# knxhome-lqfp32-v2.net
KiCad netlist of a schematic drawn in EAGLE
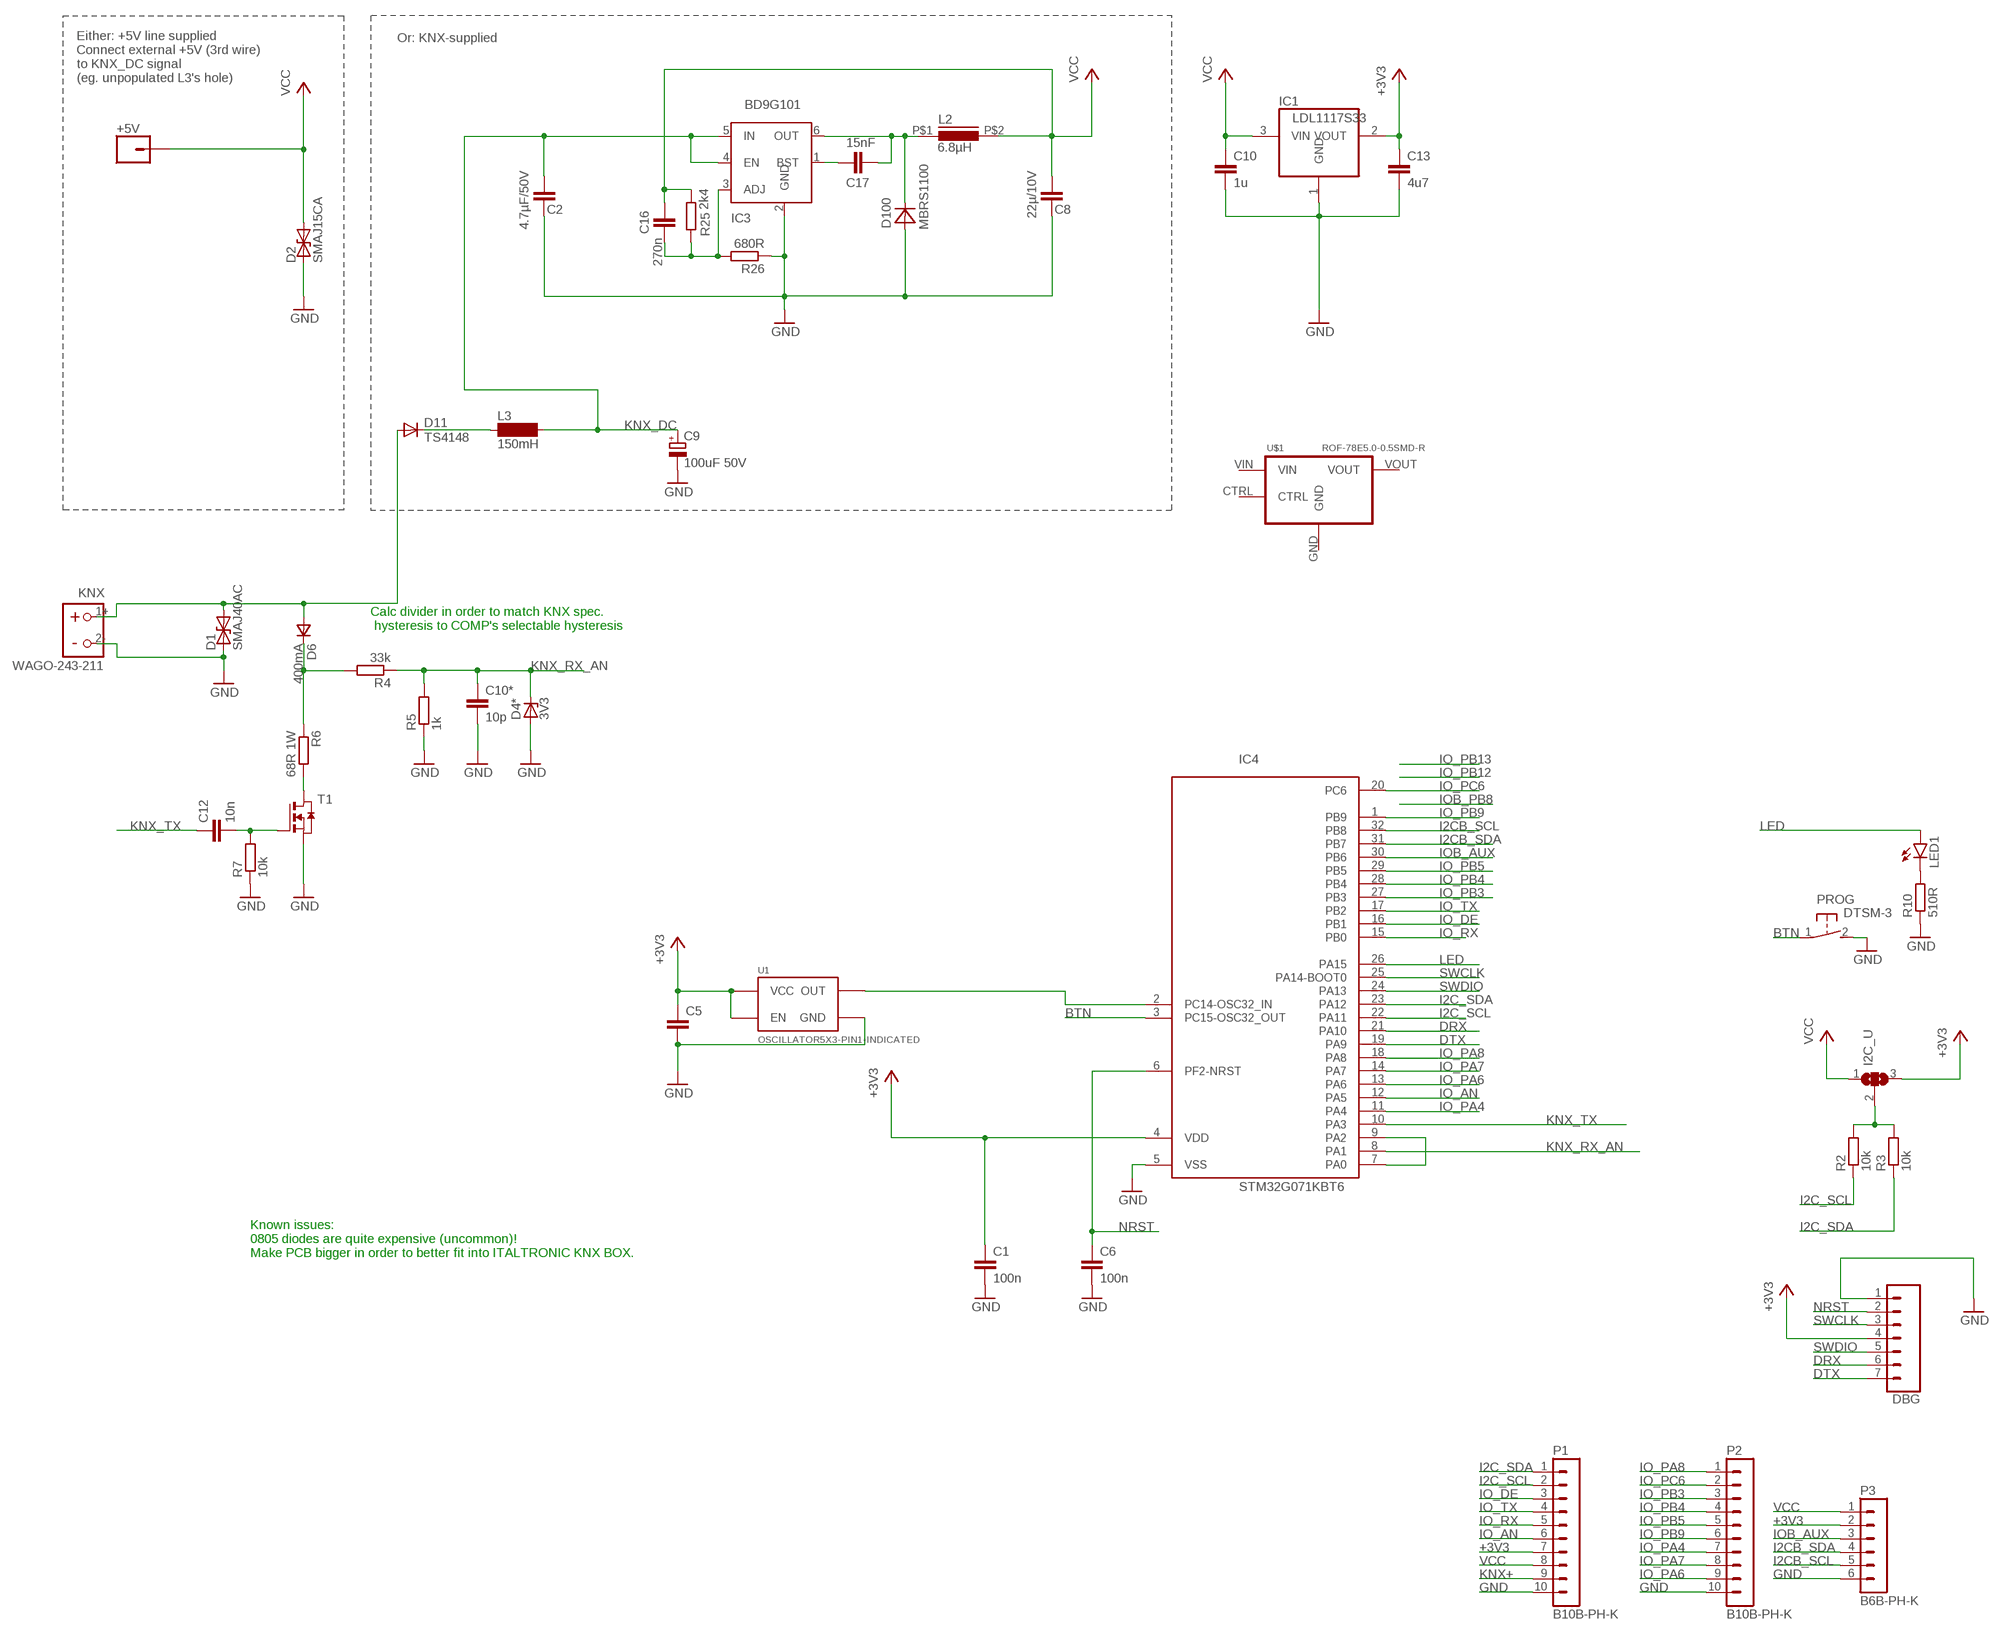
[diagram p0: schematic, sheet 1]

(export (version "E")
  (design (tool "Eeschema 10.0.6"))
  (components
    (comp (ref "+5V")
      (value "CONN_01PTH_LONGPAD")
      (footprint "eagle-import:1X01_LONGPAD")
      (libsource (lib "eagle-import") (part "CONN_01PTH_LONGPAD"))
    )
    (comp (ref "C1")
      (value "100n")
      (footprint "eagle-import:C0805")
      (libsource (lib "eagle-import") (part "C-EUC0805"))
    )
    (comp (ref "C2")
      (value "4.7µF/50V")
      (footprint "eagle-import:C0805")
      (libsource (lib "eagle-import") (part "C-EUC0805"))
    )
    (comp (ref "C5")
      (value "C-EUC0805")
      (footprint "eagle-import:C0805")
      (libsource (lib "eagle-import") (part "C-EUC0805"))
    )
    (comp (ref "C6")
      (value "100n")
      (footprint "eagle-import:C0805")
      (libsource (lib "eagle-import") (part "C-EUC0805"))
    )
    (comp (ref "C8")
      (value "22µ/10V")
      (footprint "eagle-import:C0805")
      (libsource (lib "eagle-import") (part "C-EUC0805"))
    )
    (comp (ref "C9")
      (value "100uF 50V")
      (footprint "eagle-import:E3,5-8")
      (libsource (lib "eagle-import") (part "CPOL-EUE3.5-8"))
    )
    (comp (ref "C10")
      (value "1u")
      (footprint "eagle-import:C0805")
      (libsource (lib "eagle-import") (part "C-EUC0805"))
    )
    (comp (ref "C10*")
      (value "10p")
      (footprint "eagle-import:C0805")
      (libsource (lib "eagle-import") (part "C-EUC0805"))
    )
    (comp (ref "C12")
      (value "10n")
      (footprint "eagle-import:C0805")
      (libsource (lib "eagle-import") (part "C-EUC0805"))
    )
    (comp (ref "C13")
      (value "4u7")
      (footprint "eagle-import:C0805")
      (libsource (lib "eagle-import") (part "C-EUC0805"))
    )
    (comp (ref "C16")
      (value "270n")
      (footprint "eagle-import:C0805")
      (libsource (lib "eagle-import") (part "C-EUC0805"))
    )
    (comp (ref "C17")
      (value "15nF")
      (footprint "eagle-import:C0805")
      (libsource (lib "eagle-import") (part "C-EUC0805"))
    )
    (comp (ref "D1")
      (value "SMAJ40AC")
      (footprint "eagle-import:DO-214AC")
      (libsource (lib "eagle-import") (part "SMAJ40AC"))
    )
    (comp (ref "D2")
      (value "SMAJ15CA")
      (footprint "eagle-import:DO-214AC")
      (libsource (lib "eagle-import") (part "SMAJ40AC"))
    )
    (comp (ref "D4*")
      (value "3V3")
      (footprint "eagle-import:SOT23")
      (libsource (lib "eagle-import") (part "ZENER-DIODESOT23"))
    )
    (comp (ref "D6")
      (value "400mA")
      (footprint "eagle-import:SOD323")
      (fields (field (name "MPN") "CDSOD323-T05C"))
      (libsource (lib "eagle-import") (part "DSOD323"))
    )
    (comp (ref "D11")
      (value "TS4148")
      (footprint "eagle-import:D0805")
      (libsource (lib "eagle-import") (part "DIODE-D0805"))
    )
    (comp (ref "D100")
      (value "MBRS1100")
      (footprint "eagle-import:SMA")
      (libsource (lib "eagle-import") (part "MBRA340T3"))
    )
    (comp (ref "DBG")
      (value "CONN_07LOCK")
      (footprint "eagle-import:1X07_LOCK")
      (libsource (lib "eagle-import") (part "CONN_07LOCK"))
    )
    (comp (ref "I2C_U")
      (value "SJ2W")
      (footprint "eagle-import:SJ_2")
      (libsource (lib "eagle-import") (part "SJ2W"))
    )
    (comp (ref "IC1")
      (value "LDL1117S33")
      (footprint "eagle-import:SOT223")
      (fields (field (name "MPN") "REG1117"))
      (libsource (lib "eagle-import") (part "REG1117"))
    )
    (comp (ref "IC3")
      (value "BD9G101")
      (footprint "eagle-import:SOT23-6")
      (libsource (lib "eagle-import") (part "BD9G101GBD9G101G-SOT23-6"))
    )
    (comp (ref "IC4")
      (value "STM32G071KBT6")
      (footprint "eagle-import:LQFP32")
      (libsource (lib "eagle-import") (part "STM32G071KBT6"))
    )
    (comp (ref "KNX")
      (value "WAGO-243-211")
      (footprint "eagle-import:WAGO-243-211")
      (libsource (lib "eagle-import") (part "WAGO-243-211"))
    )
    (comp (ref "L2")
      (value "6.8µH")
      (footprint "eagle-import:PIS2812")
      (libsource (lib "eagle-import") (part "IND_FASTRON_1616FPS"))
    )
    (comp (ref "L3")
      (value "150mH")
      (footprint "eagle-import:BS11_LIEGEND")
      (libsource (lib "eagle-import") (part "SD12BS11_LIEGEND"))
    )
    (comp (ref "LED1")
      (value "LEDCHIP-LED0805")
      (footprint "eagle-import:CHIP-LED0805")
      (libsource (lib "eagle-import") (part "LEDCHIP-LED0805"))
    )
    (comp (ref "P1")
      (value "B10B-PH-K")
      (footprint "eagle-import:B10B-PH-K")
      (libsource (lib "eagle-import") (part "B10B-PH-K"))
    )
    (comp (ref "P2")
      (value "B10B-PH-K")
      (footprint "eagle-import:B10B-PH-K")
      (libsource (lib "eagle-import") (part "B10B-PH-K"))
    )
    (comp (ref "P3")
      (value "B6B-PH-K")
      (footprint "eagle-import:B6B-PH-K")
      (libsource (lib "eagle-import") (part "B6B-PH-K"))
    )
    (comp (ref "PROG")
      (value "DTSM-3")
      (footprint "eagle-import:DTSM-3")
      (libsource (lib "eagle-import") (part "DTSM-3"))
    )
    (comp (ref "R2")
      (value "10k")
      (footprint "eagle-import:R0805")
      (libsource (lib "eagle-import") (part "R-EU_R0805"))
    )
    (comp (ref "R3")
      (value "10k")
      (footprint "eagle-import:R0805")
      (libsource (lib "eagle-import") (part "R-EU_R0805"))
    )
    (comp (ref "R4")
      (value "33k")
      (footprint "eagle-import:R0805")
      (libsource (lib "eagle-import") (part "R-EU_R0805"))
    )
    (comp (ref "R5")
      (value "1k")
      (footprint "eagle-import:R0805")
      (libsource (lib "eagle-import") (part "R-EU_R0805"))
    )
    (comp (ref "R6")
      (value "68R 1W")
      (footprint "eagle-import:R2512")
      (libsource (lib "eagle-import") (part "R-EU_R2512"))
    )
    (comp (ref "R7")
      (value "10k")
      (footprint "eagle-import:R0805")
      (libsource (lib "eagle-import") (part "R-EU_R0805"))
    )
    (comp (ref "R10")
      (value "510R")
      (footprint "eagle-import:R0805")
      (libsource (lib "eagle-import") (part "R-EU_R0805"))
    )
    (comp (ref "R25")
      (value "2k4")
      (footprint "eagle-import:R0805")
      (libsource (lib "eagle-import") (part "R-EU_R0805"))
    )
    (comp (ref "R26")
      (value "680R")
      (footprint "eagle-import:R0805")
      (libsource (lib "eagle-import") (part "R-EU_R0805"))
    )
    (comp (ref "T1")
      (value "NMOSSOT23")
      (footprint "eagle-import:SOT-23")
      (libsource (lib "eagle-import") (part "NMOSSOT23"))
    )
    (comp (ref "U$1")
      (value "ROF-78E5.0-0.5SMD-R")
      (footprint "eagle-import:ROF-78EX-XSMD-R")
      (libsource (lib "eagle-import") (part "ROF-78E5.0-0.5SMD-R"))
    )
    (comp (ref "U1")
      (value "OSCILLATOR5X3-PIN1-INDICATED")
      (footprint "eagle-import:CRYSTAL-OSC-SMD-5X3")
      (libsource (lib "eagle-import") (part "OSCILLATOR5X3-PIN1-INDICATED"))
    )
  )
  (nets
    (net (code "1") (name "+3V3") (class "Default")
      (node (ref "C1") (pin "1") (pinfunction "1_1") (pintype "passive"))
      (node (ref "C13") (pin "1") (pinfunction "1_1") (pintype "passive"))
      (node (ref "C5") (pin "1") (pinfunction "1_1") (pintype "passive"))
      (node (ref "DBG") (pin "4") (pinfunction "4_4") (pintype "passive"))
      (node (ref "I2C_U") (pin "3") (pinfunction "3_3") (pintype "passive"))
      (node (ref "IC1") (pin "2") (pinfunction "VOUT_2") (pintype "output"))
      (node (ref "IC4") (pin "4") (pinfunction "VDD_4") (pintype "power_in"))
      (node (ref "P1") (pin "7") (pinfunction "7_7") (pintype "passive"))
      (node (ref "P3") (pin "2") (pinfunction "2_2") (pintype "passive"))
      (node (ref "U1") (pin "1") (pinfunction "EN_1") (pintype "bidirectional"))
      (node (ref "U1") (pin "4") (pinfunction "VCC_4") (pintype "bidirectional"))
    )
    (net (code "2") (name "/BTN") (class "Default")
      (node (ref "IC4") (pin "3") (pinfunction "PC15-OSC32_OUT_3") (pintype "bidirectional"))
      (node (ref "PROG") (pin "1") (pinfunction "1_1") (pintype "passive"))
    )
    (net (code "3") (name "/DRX") (class "Default")
      (node (ref "DBG") (pin "6") (pinfunction "6_6") (pintype "passive"))
      (node (ref "IC4") (pin "21") (pinfunction "PA10_21") (pintype "bidirectional"))
    )
    (net (code "4") (name "/DTX") (class "Default")
      (node (ref "DBG") (pin "7") (pinfunction "7_7") (pintype "passive"))
      (node (ref "IC4") (pin "19") (pinfunction "PA9_19") (pintype "bidirectional"))
    )
    (net (code "5") (name "/I2CB_SCL") (class "Default")
      (node (ref "IC4") (pin "32") (pinfunction "PB8_32") (pintype "bidirectional"))
      (node (ref "P3") (pin "5") (pinfunction "5_5") (pintype "passive"))
    )
    (net (code "6") (name "/I2CB_SDA") (class "Default")
      (node (ref "IC4") (pin "31") (pinfunction "PB7_31") (pintype "bidirectional"))
      (node (ref "P3") (pin "4") (pinfunction "4_4") (pintype "passive"))
    )
    (net (code "7") (name "/I2C_SCL") (class "Default")
      (node (ref "IC4") (pin "22") (pinfunction "PA11_22") (pintype "bidirectional"))
      (node (ref "P1") (pin "2") (pinfunction "2_2") (pintype "passive"))
      (node (ref "R2") (pin "1") (pinfunction "1_1") (pintype "passive"))
    )
    (net (code "8") (name "/I2C_SDA") (class "Default")
      (node (ref "IC4") (pin "23") (pinfunction "PA12_23") (pintype "bidirectional"))
      (node (ref "P1") (pin "1") (pinfunction "1_1") (pintype "passive"))
      (node (ref "R3") (pin "1") (pinfunction "1_1") (pintype "passive"))
    )
    (net (code "9") (name "/IOB_AUX") (class "Default")
      (node (ref "IC4") (pin "30") (pinfunction "PB6_30") (pintype "bidirectional"))
      (node (ref "P3") (pin "3") (pinfunction "3_3") (pintype "passive"))
    )
    (net (code "11") (name "/IO_AN") (class "Default")
      (node (ref "IC4") (pin "12") (pinfunction "PA5_12") (pintype "bidirectional"))
      (node (ref "P1") (pin "6") (pinfunction "6_6") (pintype "passive"))
    )
    (net (code "12") (name "/IO_DE") (class "Default")
      (node (ref "IC4") (pin "16") (pinfunction "PB1_16") (pintype "bidirectional"))
      (node (ref "P1") (pin "3") (pinfunction "3_3") (pintype "passive"))
    )
    (net (code "13") (name "/IO_PA4") (class "Default")
      (node (ref "IC4") (pin "11") (pinfunction "PA4_11") (pintype "bidirectional"))
      (node (ref "P2") (pin "7") (pinfunction "7_7") (pintype "passive"))
    )
    (net (code "14") (name "/IO_PA6") (class "Default")
      (node (ref "IC4") (pin "13") (pinfunction "PA6_13") (pintype "bidirectional"))
      (node (ref "P2") (pin "9") (pinfunction "9_9") (pintype "passive"))
    )
    (net (code "15") (name "/IO_PA7") (class "Default")
      (node (ref "IC4") (pin "14") (pinfunction "PA7_14") (pintype "bidirectional"))
      (node (ref "P2") (pin "8") (pinfunction "8_8") (pintype "passive"))
    )
    (net (code "16") (name "/IO_PA8") (class "Default")
      (node (ref "IC4") (pin "18") (pinfunction "PA8_18") (pintype "bidirectional"))
      (node (ref "P2") (pin "1") (pinfunction "1_1") (pintype "passive"))
    )
    (net (code "17") (name "/IO_PB3") (class "Default")
      (node (ref "IC4") (pin "27") (pinfunction "PB3_27") (pintype "bidirectional"))
      (node (ref "P2") (pin "3") (pinfunction "3_3") (pintype "passive"))
    )
    (net (code "18") (name "/IO_PB4") (class "Default")
      (node (ref "IC4") (pin "28") (pinfunction "PB4_28") (pintype "bidirectional"))
      (node (ref "P2") (pin "4") (pinfunction "4_4") (pintype "passive"))
    )
    (net (code "19") (name "/IO_PB5") (class "Default")
      (node (ref "IC4") (pin "29") (pinfunction "PB5_29") (pintype "bidirectional"))
      (node (ref "P2") (pin "5") (pinfunction "5_5") (pintype "passive"))
    )
    (net (code "20") (name "/IO_PB9") (class "Default")
      (node (ref "IC4") (pin "1") (pinfunction "PB9_1") (pintype "bidirectional"))
      (node (ref "P2") (pin "6") (pinfunction "6_6") (pintype "passive"))
    )
    (net (code "23") (name "/IO_PC6") (class "Default")
      (node (ref "IC4") (pin "20") (pinfunction "PC6_20") (pintype "bidirectional"))
      (node (ref "P2") (pin "2") (pinfunction "2_2") (pintype "passive"))
    )
    (net (code "24") (name "/IO_RX") (class "Default")
      (node (ref "IC4") (pin "15") (pinfunction "PB0_15") (pintype "bidirectional"))
      (node (ref "P1") (pin "5") (pinfunction "5_5") (pintype "passive"))
    )
    (net (code "25") (name "/IO_TX") (class "Default")
      (node (ref "IC4") (pin "17") (pinfunction "PB2_17") (pintype "bidirectional"))
      (node (ref "P1") (pin "4") (pinfunction "4_4") (pintype "passive"))
    )
    (net (code "26") (name "/KNX+") (class "Default")
      (node (ref "D1") (pin "C") (pinfunction "C_C") (pintype "passive"))
      (node (ref "D11") (pin "A") (pinfunction "A_A") (pintype "passive"))
      (node (ref "D6") (pin "2") (pinfunction "A_2") (pintype "passive"))
      (node (ref "KNX") (pin "1+") (pinfunction "1+_1+") (pintype "passive"))
      (node (ref "P1") (pin "9") (pinfunction "9_9") (pintype "passive"))
    )
    (net (code "27") (name "/KNX_DC") (class "Default")
      (node (ref "C2") (pin "2") (pinfunction "2_2") (pintype "passive"))
      (node (ref "C9") (pin "+") (pinfunction "+_+") (pintype "passive"))
      (node (ref "IC3") (pin "4") (pinfunction "EN_4") (pintype "input"))
      (node (ref "IC3") (pin "5") (pinfunction "IN_5") (pintype "input"))
      (node (ref "L3") (pin "2") (pinfunction "2_2") (pintype "passive"))
    )
    (net (code "28") (name "/KNX_RX_AN") (class "Default")
      (node (ref "C10*") (pin "1") (pinfunction "1_1") (pintype "passive"))
      (node (ref "D4*") (pin "3") (pinfunction "C_3") (pintype "passive"))
      (node (ref "IC4") (pin "8") (pinfunction "PA1_8") (pintype "bidirectional"))
      (node (ref "R4") (pin "1") (pinfunction "1_1") (pintype "passive"))
      (node (ref "R5") (pin "2") (pinfunction "2_2") (pintype "passive"))
    )
    (net (code "29") (name "/KNX_TX") (class "Default")
      (node (ref "C12") (pin "1") (pinfunction "1_1") (pintype "passive"))
      (node (ref "IC4") (pin "10") (pinfunction "PA3_10") (pintype "bidirectional"))
    )
    (net (code "30") (name "/LED") (class "Default")
      (node (ref "IC4") (pin "26") (pinfunction "PA15_26") (pintype "bidirectional"))
      (node (ref "LED1") (pin "A") (pinfunction "A_A") (pintype "passive"))
    )
    (net (code "31") (name "/NRST") (class "Default")
      (node (ref "C6") (pin "1") (pinfunction "1_1") (pintype "passive"))
      (node (ref "DBG") (pin "2") (pinfunction "2_2") (pintype "passive"))
      (node (ref "IC4") (pin "6") (pinfunction "PF2-NRST_6") (pintype "bidirectional"))
    )
    (net (code "32") (name "/SWCLK") (class "Default")
      (node (ref "DBG") (pin "3") (pinfunction "3_3") (pintype "passive"))
      (node (ref "IC4") (pin "25") (pinfunction "PA14-BOOT0_25") (pintype "bidirectional"))
    )
    (net (code "33") (name "/SWDIO") (class "Default")
      (node (ref "DBG") (pin "5") (pinfunction "5_5") (pintype "passive"))
      (node (ref "IC4") (pin "24") (pinfunction "PA13_24") (pintype "bidirectional"))
    )
    (net (code "34") (name "GND") (class "Default")
      (node (ref "C1") (pin "2") (pinfunction "2_2") (pintype "passive"))
      (node (ref "C10") (pin "2") (pinfunction "2_2") (pintype "passive"))
      (node (ref "C10*") (pin "2") (pinfunction "2_2") (pintype "passive"))
      (node (ref "C13") (pin "2") (pinfunction "2_2") (pintype "passive"))
      (node (ref "C2") (pin "1") (pinfunction "1_1") (pintype "passive"))
      (node (ref "C5") (pin "2") (pinfunction "2_2") (pintype "passive"))
      (node (ref "C6") (pin "2") (pinfunction "2_2") (pintype "passive"))
      (node (ref "C8") (pin "1") (pinfunction "1_1") (pintype "passive"))
      (node (ref "C9") (pin "-") (pinfunction "-_-") (pintype "passive"))
      (node (ref "D1") (pin "A") (pinfunction "A_A") (pintype "passive"))
      (node (ref "D100") (pin "A") (pinfunction "A_A") (pintype "passive"))
      (node (ref "D2") (pin "A") (pinfunction "A_A") (pintype "passive"))
      (node (ref "D4*") (pin "1") (pinfunction "A_1") (pintype "passive"))
      (node (ref "DBG") (pin "1") (pinfunction "1_1") (pintype "passive"))
      (node (ref "IC1") (pin "1") (pinfunction "GND_1") (pintype "power_in"))
      (node (ref "IC3") (pin "2") (pinfunction "GND_2") (pintype "power_in"))
      (node (ref "IC4") (pin "5") (pinfunction "VSS_5") (pintype "power_in"))
      (node (ref "KNX") (pin "2-") (pinfunction "2-_2-") (pintype "passive"))
      (node (ref "P1") (pin "10") (pinfunction "10_10") (pintype "passive"))
      (node (ref "P2") (pin "10") (pinfunction "10_10") (pintype "passive"))
      (node (ref "P3") (pin "6") (pinfunction "6_6") (pintype "passive"))
      (node (ref "PROG") (pin "2") (pinfunction "2_2") (pintype "passive"))
      (node (ref "R10") (pin "1") (pinfunction "1_1") (pintype "passive"))
      (node (ref "R26") (pin "1") (pinfunction "1_1") (pintype "passive"))
      (node (ref "R5") (pin "1") (pinfunction "1_1") (pintype "passive"))
      (node (ref "R7") (pin "1") (pinfunction "1_1") (pintype "passive"))
      (node (ref "T1") (pin "2") (pinfunction "S_2") (pintype "passive"))
      (node (ref "U1") (pin "2") (pinfunction "GND_2") (pintype "bidirectional"))
    )
    (net (code "35") (name "Net-(D6-C)") (class "Default")
      (node (ref "D6") (pin "1") (pinfunction "C_1") (pintype "passive"))
      (node (ref "R4") (pin "2") (pinfunction "2_2") (pintype "passive"))
      (node (ref "R6") (pin "1") (pinfunction "1_1") (pintype "passive"))
    )
    (net (code "36") (name "Net-(D11-PadC)") (class "Default")
      (node (ref "D11") (pin "C") (pinfunction "C_C") (pintype "passive"))
      (node (ref "L3") (pin "1") (pinfunction "1_1") (pintype "passive"))
    )
    (net (code "37") (name "Net-(I2C_U-Pad2)") (class "Default")
      (node (ref "I2C_U") (pin "2") (pinfunction "2_2") (pintype "passive"))
      (node (ref "R2") (pin "2") (pinfunction "2_2") (pintype "passive"))
      (node (ref "R3") (pin "2") (pinfunction "2_2") (pintype "passive"))
    )
    (net (code "38") (name "Net-(IC3-ADJ)") (class "Default")
      (node (ref "C16") (pin "1") (pinfunction "1_1") (pintype "passive"))
      (node (ref "IC3") (pin "3") (pinfunction "ADJ_3") (pintype "passive"))
      (node (ref "R25") (pin "1") (pinfunction "1_1") (pintype "passive"))
      (node (ref "R26") (pin "2") (pinfunction "2_2") (pintype "passive"))
    )
    (net (code "39") (name "Net-(IC3-BST)") (class "Default")
      (node (ref "C17") (pin "2") (pinfunction "2_2") (pintype "passive"))
      (node (ref "IC3") (pin "1") (pinfunction "BST_1") (pintype "output"))
    )
    (net (code "40") (name "Net-(IC3-OUT)") (class "Default")
      (node (ref "C17") (pin "1") (pinfunction "1_1") (pintype "passive"))
      (node (ref "D100") (pin "C") (pinfunction "C_C") (pintype "passive"))
      (node (ref "IC3") (pin "6") (pinfunction "OUT_6") (pintype "output"))
      (node (ref "L2") (pin "P$1") (pinfunction "1_P$1") (pintype "passive"))
    )
    (net (code "41") (name "Net-(IC4-PA0)") (class "Default")
      (node (ref "IC4") (pin "7") (pinfunction "PA0_7") (pintype "bidirectional"))
      (node (ref "IC4") (pin "9") (pinfunction "PA2_9") (pintype "bidirectional"))
    )
    (net (code "42") (name "Net-(IC4-PC14-OSC32_IN)") (class "Default")
      (node (ref "IC4") (pin "2") (pinfunction "PC14-OSC32_IN_2") (pintype "bidirectional"))
      (node (ref "U1") (pin "3") (pinfunction "OUT_3") (pintype "bidirectional"))
    )
    (net (code "43") (name "Net-(LED1-PadC)") (class "Default")
      (node (ref "LED1") (pin "C") (pinfunction "C_C") (pintype "passive"))
      (node (ref "R10") (pin "2") (pinfunction "2_2") (pintype "passive"))
    )
    (net (code "44") (name "Net-(T1-D)") (class "Default")
      (node (ref "R6") (pin "2") (pinfunction "2_2") (pintype "passive"))
      (node (ref "T1") (pin "1") (pinfunction "D_1") (pintype "passive"))
    )
    (net (code "45") (name "Net-(T1-G)") (class "Default")
      (node (ref "C12") (pin "2") (pinfunction "2_2") (pintype "passive"))
      (node (ref "R7") (pin "2") (pinfunction "2_2") (pintype "passive"))
      (node (ref "T1") (pin "3") (pinfunction "G_3") (pintype "passive"))
    )
    (net (code "46") (name "VCC") (class "Default")
      (node (ref "+5V") (pin "1") (pinfunction "1_1") (pintype "passive"))
      (node (ref "C10") (pin "1") (pinfunction "1_1") (pintype "passive"))
      (node (ref "C16") (pin "2") (pinfunction "2_2") (pintype "passive"))
      (node (ref "C8") (pin "2") (pinfunction "2_2") (pintype "passive"))
      (node (ref "D2") (pin "C") (pinfunction "C_C") (pintype "passive"))
      (node (ref "I2C_U") (pin "1") (pinfunction "1_1") (pintype "passive"))
      (node (ref "IC1") (pin "3") (pinfunction "VIN_3") (pintype "input"))
      (node (ref "L2") (pin "P$2") (pinfunction "2_P$2") (pintype "passive"))
      (node (ref "P1") (pin "8") (pinfunction "8_8") (pintype "passive"))
      (node (ref "P3") (pin "1") (pinfunction "1_1") (pintype "passive"))
      (node (ref "R25") (pin "2") (pinfunction "2_2") (pintype "passive"))
    )
    (net (code "47") (name "unconnected-(U$1-PadCTRL)") (class "Default")
      (node (ref "U$1") (pin "CTRL") (pinfunction "CTRL_CTRL") (pintype "bidirectional"))
    )
    (net (code "48") (name "unconnected-(U$1-PadGND)") (class "Default")
      (node (ref "U$1") (pin "GND") (pinfunction "GND_GND") (pintype "bidirectional"))
    )
    (net (code "49") (name "unconnected-(U$1-PadVIN)") (class "Default")
      (node (ref "U$1") (pin "VIN") (pinfunction "VIN_VIN") (pintype "bidirectional"))
    )
    (net (code "50") (name "unconnected-(U$1-PadVOUT)") (class "Default")
      (node (ref "U$1") (pin "VOUT") (pinfunction "VOUT_VOUT") (pintype "bidirectional"))
    )
  )
)
